# USB_SWITCH.net
KiCad netlist of a schematic drawn in Altium Designer
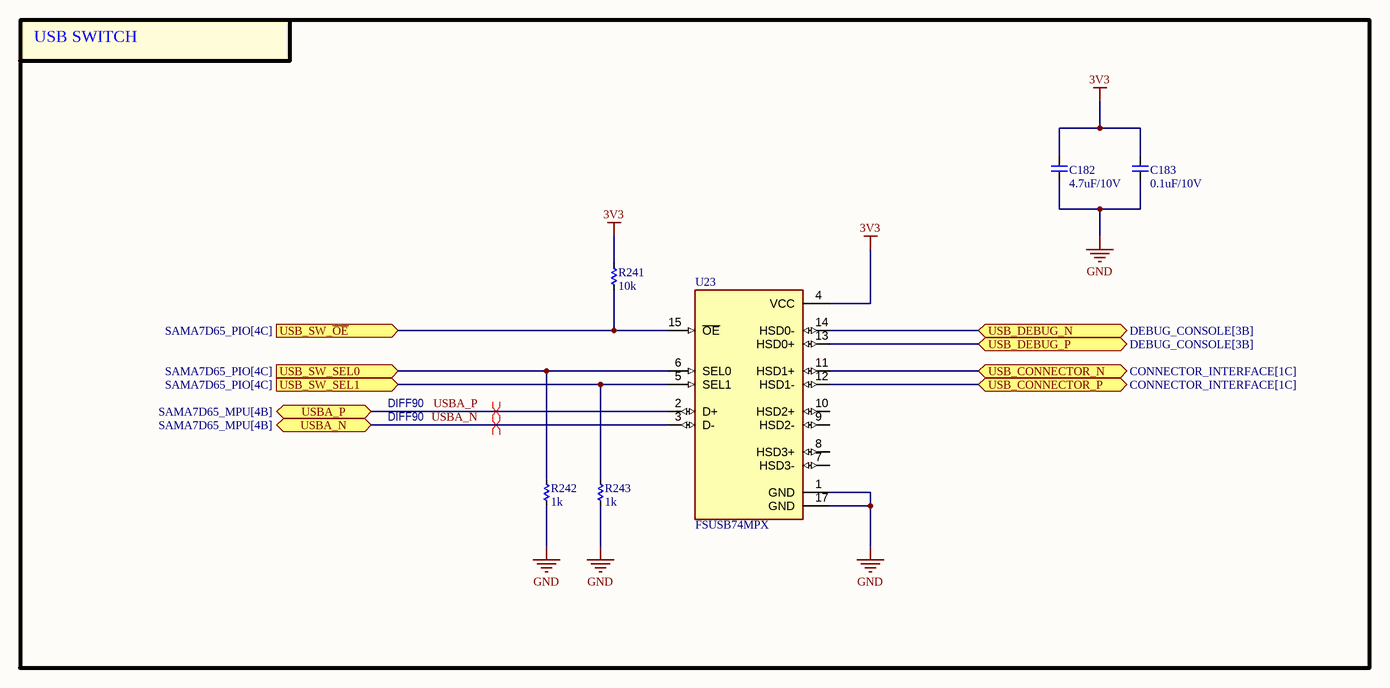
[diagram p0: USB_SWITCH.SchDoc]

(export (version "E")
  (design (tool "Eeschema 10.0.6"))
  (components
    (comp (ref "C182")
      (value "4.7uF/10V")
      (footprint "CAP_C_1005X50_L")
      (description "CAP CHIP")
      (libsource (lib "IFBschelib") (part "_CAP_C_2"))
    )
    (comp (ref "C183")
      (value "0.1uF/10V")
      (footprint "CAP_C_1005X50_L")
      (description "CAP CHIP")
      (libsource (lib "IFBschelib") (part "_CAP_C_2"))
    )
    (comp (ref "R241")
      (value "10k")
      (footprint "RES_C_1005X40")
      (description "RES")
      (libsource (lib "IFBschelib") (part "_RES_B_2"))
    )
    (comp (ref "R242")
      (value "1k")
      (footprint "RES_C_1005X40")
      (description "RES")
      (libsource (lib "IFBschelib") (part "_RES_B_2"))
    )
    (comp (ref "R243")
      (value "1k")
      (footprint "RES_C_1005X40")
      (description "RES")
      (libsource (lib "IFBschelib") (part "_RES_B_2"))
    )
    (comp (ref "U23")
      (value "FSUSB74MPX")
      (footprint "QFN50P300X300X80-17N")
      (description "USB Switch IC 1 Channel 16-MLP (3x3)")
      (fields (field (name "MF") "ON Semiconductor"))
      (libsource (lib "IFBschelib") (part "IC_USB_SW_FSUSB74MPX"))
    )
  )
  (nets
    (net (code "1") (name "/USBA_N") (class "Default")
      (node (ref "U23") (pin "3") (pinfunction "D-_3") (pintype "bidirectional"))
    )
    (net (code "2") (name "/USBA_P") (class "Default")
      (node (ref "U23") (pin "2") (pinfunction "D+_2") (pintype "bidirectional"))
    )
    (net (code "3") (name "/USB_CONNECTOR_N") (class "Default")
      (node (ref "U23") (pin "11") (pinfunction "HSD1+_11") (pintype "bidirectional"))
    )
    (net (code "4") (name "/USB_CONNECTOR_P") (class "Default")
      (node (ref "U23") (pin "12") (pinfunction "HSD1-_12") (pintype "bidirectional"))
    )
    (net (code "5") (name "/USB_DEBUG_N") (class "Default")
      (node (ref "U23") (pin "14") (pinfunction "HSD0-_14") (pintype "bidirectional"))
    )
    (net (code "6") (name "/USB_DEBUG_P") (class "Default")
      (node (ref "U23") (pin "13") (pinfunction "HSD0+_13") (pintype "bidirectional"))
    )
    (net (code "7") (name "/USB_SW_SEL0") (class "Default")
      (node (ref "R242") (pin "2") (pinfunction "2_2") (pintype "passive"))
      (node (ref "U23") (pin "6") (pinfunction "SEL0_6") (pintype "input"))
    )
    (net (code "8") (name "/USB_SW_SEL1") (class "Default")
      (node (ref "R243") (pin "2") (pinfunction "2_2") (pintype "passive"))
      (node (ref "U23") (pin "5") (pinfunction "SEL1_5") (pintype "input"))
    )
    (net (code "9") (name "/USB_SW_~{OE}") (class "Default")
      (node (ref "R241") (pin "1") (pinfunction "1_1") (pintype "passive"))
      (node (ref "U23") (pin "15") (pinfunction "~{OE}_15") (pintype "input"))
    )
    (net (code "10") (name "3V3") (class "Default")
      (node (ref "C182") (pin "2") (pinfunction "2_2") (pintype "passive"))
      (node (ref "C183") (pin "2") (pinfunction "2_2") (pintype "passive"))
      (node (ref "R241") (pin "2") (pinfunction "2_2") (pintype "passive"))
      (node (ref "U23") (pin "4") (pinfunction "VCC_4") (pintype "power_in"))
    )
    (net (code "11") (name "GND") (class "Default")
      (node (ref "C182") (pin "1") (pinfunction "1_1") (pintype "passive"))
      (node (ref "C183") (pin "1") (pinfunction "1_1") (pintype "passive"))
      (node (ref "R242") (pin "1") (pinfunction "1_1") (pintype "passive"))
      (node (ref "R243") (pin "1") (pinfunction "1_1") (pintype "passive"))
      (node (ref "U23") (pin "1") (pinfunction "GND_1") (pintype "power_in"))
      (node (ref "U23") (pin "17") (pinfunction "GND_17") (pintype "power_in"))
    )
    (net (code "12") (name "unconnected-(U23-HSD2+-Pad10)") (class "Default")
      (node (ref "U23") (pin "10") (pinfunction "HSD2+_10") (pintype "bidirectional"))
    )
    (net (code "13") (name "unconnected-(U23-HSD2--Pad9)") (class "Default")
      (node (ref "U23") (pin "9") (pinfunction "HSD2-_9") (pintype "bidirectional"))
    )
    (net (code "14") (name "unconnected-(U23-HSD3+-Pad8)") (class "Default")
      (node (ref "U23") (pin "8") (pinfunction "HSD3+_8") (pintype "bidirectional"))
    )
    (net (code "15") (name "unconnected-(U23-HSD3--Pad7)") (class "Default")
      (node (ref "U23") (pin "7") (pinfunction "HSD3-_7") (pintype "bidirectional"))
    )
  )
)
